# New_Project_2025-08-05.net
KiCad netlist of a schematic drawn in EasyEDA Pro
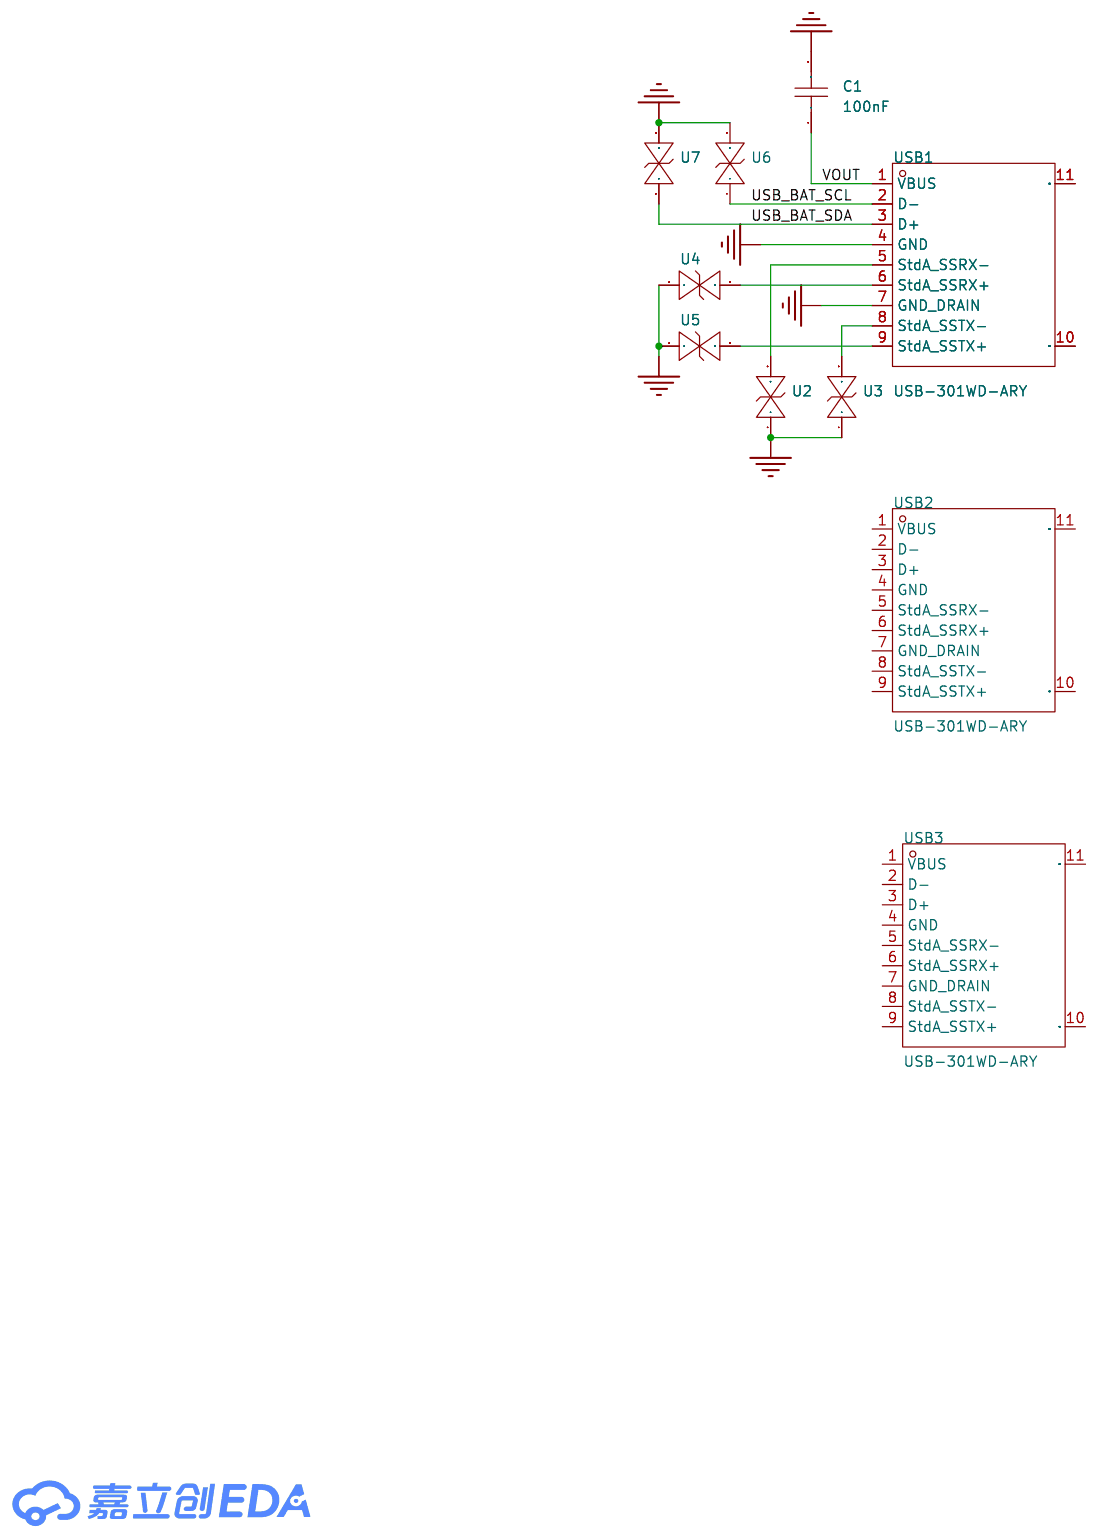
[diagram p0: schematic sheet]

(export (version "E")
  (design (tool "Eeschema 10.0.6"))
  (components
    (comp (ref "C1")
      (value "100nF")
      (footprint "easyedapro:C0603")
      (libsource (lib "easyedapro") (part "Capacitance"))
    )
    (comp (ref "U2")
      (value "ESD5451N")
      (footprint "easyedapro:X1-DFN1006-2_L1.0-W0.6-P0.65-BI")
      (description "极性:双向;反向截止电压(Vrwm):5V;钳位电压:13V;峰值脉冲电流(Ipp):5.5A;峰值脉冲功率(Ppp):90W;击穿电压:8.4V;")
      (fields (field (name "Manufacturer") "TECH PUBLIC(台舟)"))
      (libsource (lib "easyedapro") (part "ESD5451N_C2936977"))
    )
    (comp (ref "U3")
      (value "ESD5451N")
      (footprint "easyedapro:X1-DFN1006-2_L1.0-W0.6-P0.65-BI")
      (description "极性:双向;反向截止电压(Vrwm):5V;钳位电压:13V;峰值脉冲电流(Ipp):5.5A;峰值脉冲功率(Ppp):90W;击穿电压:8.4V;")
      (fields (field (name "Manufacturer") "TECH PUBLIC(台舟)"))
      (libsource (lib "easyedapro") (part "ESD5451N_C2936977"))
    )
    (comp (ref "U4")
      (value "ESD5451N")
      (footprint "easyedapro:X1-DFN1006-2_L1.0-W0.6-P0.65-BI")
      (description "极性:双向;反向截止电压(Vrwm):5V;钳位电压:13V;峰值脉冲电流(Ipp):5.5A;峰值脉冲功率(Ppp):90W;击穿电压:8.4V;")
      (fields (field (name "Manufacturer") "TECH PUBLIC(台舟)"))
      (libsource (lib "easyedapro") (part "ESD5451N_C2936977"))
    )
    (comp (ref "U5")
      (value "ESD5451N")
      (footprint "easyedapro:X1-DFN1006-2_L1.0-W0.6-P0.65-BI")
      (description "极性:双向;反向截止电压(Vrwm):5V;钳位电压:13V;峰值脉冲电流(Ipp):5.5A;峰值脉冲功率(Ppp):90W;击穿电压:8.4V;")
      (fields (field (name "Manufacturer") "TECH PUBLIC(台舟)"))
      (libsource (lib "easyedapro") (part "ESD5451N_C2936977"))
    )
    (comp (ref "U6")
      (value "ESD5451N")
      (footprint "easyedapro:X1-DFN1006-2_L1.0-W0.6-P0.65-BI")
      (description "极性:双向;反向截止电压(Vrwm):5V;钳位电压:13V;峰值脉冲电流(Ipp):5.5A;峰值脉冲功率(Ppp):90W;击穿电压:8.4V;")
      (fields (field (name "Manufacturer") "TECH PUBLIC(台舟)"))
      (libsource (lib "easyedapro") (part "ESD5451N_C2936977"))
    )
    (comp (ref "U7")
      (value "ESD5451N")
      (footprint "easyedapro:X1-DFN1006-2_L1.0-W0.6-P0.65-BI")
      (description "极性:双向;反向截止电压(Vrwm):5V;钳位电压:13V;峰值脉冲电流(Ipp):5.5A;峰值脉冲功率(Ppp):90W;击穿电压:8.4V;")
      (fields (field (name "Manufacturer") "TECH PUBLIC(台舟)"))
      (libsource (lib "easyedapro") (part "ESD5451N_C2936977"))
    )
    (comp (ref "USB1")
      (value "USB-301WD-ARY")
      (footprint "easyedapro:USB-TH_XUNPU_USB-301WD-ARY")
      (fields (field (name "Manufacturer") "XUNPU(讯普)"))
      (libsource (lib "easyedapro") (part "USB-301WD-ARY"))
    )
    (comp (ref "USB2")
      (value "USB-301WD-ARY")
      (footprint "easyedapro:USB-TH_XUNPU_USB-301WD-ARY")
      (fields (field (name "Manufacturer") "XUNPU(讯普)"))
      (libsource (lib "easyedapro") (part "USB-301WD-ARY"))
    )
    (comp (ref "USB3")
      (value "USB-301WD-ARY")
      (footprint "easyedapro:USB-TH_XUNPU_USB-301WD-ARY")
      (fields (field (name "Manufacturer") "XUNPU(讯普)"))
      (libsource (lib "easyedapro") (part "USB-301WD-ARY"))
    )
  )
  (nets
    (net (code "1") (name "/USB_BAT_SCL") (class "Default")
      (node (ref "U6") (pin "1") (pinfunction "1_1") (pintype "unspecified"))
      (node (ref "USB1") (pin "2") (pinfunction "D-_2") (pintype "unspecified"))
    )
    (net (code "2") (name "/USB_BAT_SDA") (class "Default")
      (node (ref "U7") (pin "1") (pinfunction "1_1") (pintype "unspecified"))
      (node (ref "USB1") (pin "3") (pinfunction "D+_3") (pintype "unspecified"))
    )
    (net (code "3") (name "/VOUT") (class "Default")
      (node (ref "C1") (pin "1") (pinfunction "1_1") (pintype "input"))
      (node (ref "USB1") (pin "1") (pinfunction "VBUS_1") (pintype "unspecified"))
    )
    (net (code "4") (name "GND") (class "Default")
      (node (ref "C1") (pin "2") (pinfunction "2_2") (pintype "input"))
      (node (ref "U2") (pin "1") (pinfunction "1_1") (pintype "unspecified"))
      (node (ref "U3") (pin "1") (pinfunction "1_1") (pintype "unspecified"))
      (node (ref "U4") (pin "1") (pinfunction "1_1") (pintype "unspecified"))
      (node (ref "U5") (pin "1") (pinfunction "1_1") (pintype "unspecified"))
      (node (ref "U6") (pin "2") (pinfunction "2_2") (pintype "unspecified"))
      (node (ref "U7") (pin "2") (pinfunction "2_2") (pintype "unspecified"))
      (node (ref "USB1") (pin "4") (pinfunction "GND_4") (pintype "unspecified"))
      (node (ref "USB1") (pin "7") (pinfunction "GND_DRAIN_7") (pintype "unspecified"))
    )
    (net (code "5") (name "Net-(USB1-StdA_SSRX+)") (class "Default")
      (node (ref "U4") (pin "2") (pinfunction "2_2") (pintype "unspecified"))
      (node (ref "USB1") (pin "6") (pinfunction "StdA_SSRX+_6") (pintype "unspecified"))
    )
    (net (code "6") (name "Net-(USB1-StdA_SSRX-)") (class "Default")
      (node (ref "U2") (pin "2") (pinfunction "2_2") (pintype "unspecified"))
      (node (ref "USB1") (pin "5") (pinfunction "StdA_SSRX-_5") (pintype "unspecified"))
    )
    (net (code "7") (name "Net-(USB1-StdA_SSTX+)") (class "Default")
      (node (ref "U5") (pin "2") (pinfunction "2_2") (pintype "unspecified"))
      (node (ref "USB1") (pin "9") (pinfunction "StdA_SSTX+_9") (pintype "unspecified"))
    )
    (net (code "8") (name "Net-(USB1-StdA_SSTX-)") (class "Default")
      (node (ref "U3") (pin "2") (pinfunction "2_2") (pintype "unspecified"))
      (node (ref "USB1") (pin "8") (pinfunction "StdA_SSTX-_8") (pintype "unspecified"))
    )
    (net (code "9") (name "unconnected-(USB1-SHIELD-Pad10)") (class "Default")
      (node (ref "USB1") (pin "10") (pinfunction "SHIELD_10") (pintype "unspecified"))
    )
    (net (code "10") (name "unconnected-(USB1-SHIELD-Pad11)") (class "Default")
      (node (ref "USB1") (pin "11") (pinfunction "SHIELD_11") (pintype "unspecified"))
    )
    (net (code "11") (name "unconnected-(USB2-D+-Pad3)") (class "Default")
      (node (ref "USB2") (pin "3") (pinfunction "D+_3") (pintype "unspecified"))
    )
    (net (code "12") (name "unconnected-(USB2-D--Pad2)") (class "Default")
      (node (ref "USB2") (pin "2") (pinfunction "D-_2") (pintype "unspecified"))
    )
    (net (code "13") (name "unconnected-(USB2-GND-Pad4)") (class "Default")
      (node (ref "USB2") (pin "4") (pinfunction "GND_4") (pintype "unspecified"))
    )
    (net (code "14") (name "unconnected-(USB2-GND_DRAIN-Pad7)") (class "Default")
      (node (ref "USB2") (pin "7") (pinfunction "GND_DRAIN_7") (pintype "unspecified"))
    )
    (net (code "15") (name "unconnected-(USB2-SHIELD-Pad10)") (class "Default")
      (node (ref "USB2") (pin "10") (pinfunction "SHIELD_10") (pintype "unspecified"))
    )
    (net (code "16") (name "unconnected-(USB2-SHIELD-Pad11)") (class "Default")
      (node (ref "USB2") (pin "11") (pinfunction "SHIELD_11") (pintype "unspecified"))
    )
    (net (code "17") (name "unconnected-(USB2-StdA_SSRX+-Pad6)") (class "Default")
      (node (ref "USB2") (pin "6") (pinfunction "StdA_SSRX+_6") (pintype "unspecified"))
    )
    (net (code "18") (name "unconnected-(USB2-StdA_SSRX--Pad5)") (class "Default")
      (node (ref "USB2") (pin "5") (pinfunction "StdA_SSRX-_5") (pintype "unspecified"))
    )
    (net (code "19") (name "unconnected-(USB2-StdA_SSTX+-Pad9)") (class "Default")
      (node (ref "USB2") (pin "9") (pinfunction "StdA_SSTX+_9") (pintype "unspecified"))
    )
    (net (code "20") (name "unconnected-(USB2-StdA_SSTX--Pad8)") (class "Default")
      (node (ref "USB2") (pin "8") (pinfunction "StdA_SSTX-_8") (pintype "unspecified"))
    )
    (net (code "21") (name "unconnected-(USB2-VBUS-Pad1)") (class "Default")
      (node (ref "USB2") (pin "1") (pinfunction "VBUS_1") (pintype "unspecified"))
    )
    (net (code "22") (name "unconnected-(USB3-D+-Pad3)") (class "Default")
      (node (ref "USB3") (pin "3") (pinfunction "D+_3") (pintype "unspecified"))
    )
    (net (code "23") (name "unconnected-(USB3-D--Pad2)") (class "Default")
      (node (ref "USB3") (pin "2") (pinfunction "D-_2") (pintype "unspecified"))
    )
    (net (code "24") (name "unconnected-(USB3-GND-Pad4)") (class "Default")
      (node (ref "USB3") (pin "4") (pinfunction "GND_4") (pintype "unspecified"))
    )
    (net (code "25") (name "unconnected-(USB3-GND_DRAIN-Pad7)") (class "Default")
      (node (ref "USB3") (pin "7") (pinfunction "GND_DRAIN_7") (pintype "unspecified"))
    )
    (net (code "26") (name "unconnected-(USB3-SHIELD-Pad10)") (class "Default")
      (node (ref "USB3") (pin "10") (pinfunction "SHIELD_10") (pintype "unspecified"))
    )
    (net (code "27") (name "unconnected-(USB3-SHIELD-Pad11)") (class "Default")
      (node (ref "USB3") (pin "11") (pinfunction "SHIELD_11") (pintype "unspecified"))
    )
    (net (code "28") (name "unconnected-(USB3-StdA_SSRX+-Pad6)") (class "Default")
      (node (ref "USB3") (pin "6") (pinfunction "StdA_SSRX+_6") (pintype "unspecified"))
    )
    (net (code "29") (name "unconnected-(USB3-StdA_SSRX--Pad5)") (class "Default")
      (node (ref "USB3") (pin "5") (pinfunction "StdA_SSRX-_5") (pintype "unspecified"))
    )
    (net (code "30") (name "unconnected-(USB3-StdA_SSTX+-Pad9)") (class "Default")
      (node (ref "USB3") (pin "9") (pinfunction "StdA_SSTX+_9") (pintype "unspecified"))
    )
    (net (code "31") (name "unconnected-(USB3-StdA_SSTX--Pad8)") (class "Default")
      (node (ref "USB3") (pin "8") (pinfunction "StdA_SSTX-_8") (pintype "unspecified"))
    )
    (net (code "32") (name "unconnected-(USB3-VBUS-Pad1)") (class "Default")
      (node (ref "USB3") (pin "1") (pinfunction "VBUS_1") (pintype "unspecified"))
    )
  )
)
